# TS5USBC41.net
KiCad netlist of a schematic drawn in Altium Designer
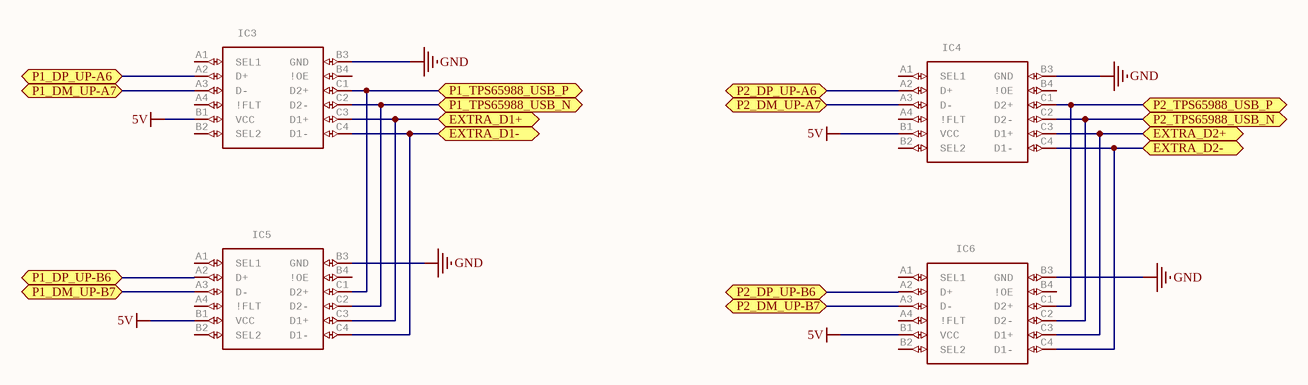
[diagram p0: TS5USBC41.SchDoc]

(export (version "E")
  (design (tool "Eeschema 10.0.6"))
  (components
    (comp (ref "IC3")
      (value "Dual 2:1 USB 2.0 Mux/DeMux or Single Ended Cross Switch With 20-V/24-V OVP   Source:  Datasheet")
      (footprint "BGA12C40P4X3_160X120X62")
      (fields
        (field (name "MANUFACTURER_PART_NUMBER") "TS5USBC410IYFFR")
        (field (name "MOUSER_PART_NUMBER") "595-TS5USBC410IYFFR")
      )
      (libsource (lib "TS5USBC410IYFFR.Library") (part "TS5USBC410IYFFR"))
    )
    (comp (ref "IC4")
      (value "Dual 2:1 USB 2.0 Mux/DeMux or Single Ended Cross Switch With 20-V/24-V OVP   Source:  Datasheet")
      (footprint "BGA12C40P4X3_160X120X62")
      (fields
        (field (name "MANUFACTURER_PART_NUMBER") "TS5USBC410IYFFR")
        (field (name "MOUSER_PART_NUMBER") "595-TS5USBC410IYFFR")
      )
      (libsource (lib "TS5USBC410IYFFR.Library") (part "TS5USBC410IYFFR"))
    )
    (comp (ref "IC5")
      (value "Dual 2:1 USB 2.0 Mux/DeMux or Single Ended Cross Switch With 20-V/24-V OVP   Source:  Datasheet")
      (footprint "BGA12C40P4X3_160X120X62")
      (fields
        (field (name "MANUFACTURER_PART_NUMBER") "TS5USBC410IYFFR")
        (field (name "MOUSER_PART_NUMBER") "595-TS5USBC410IYFFR")
      )
      (libsource (lib "TS5USBC410IYFFR.Library") (part "TS5USBC410IYFFR"))
    )
    (comp (ref "IC6")
      (value "Dual 2:1 USB 2.0 Mux/DeMux or Single Ended Cross Switch With 20-V/24-V OVP   Source:  Datasheet")
      (footprint "BGA12C40P4X3_160X120X62")
      (fields
        (field (name "MANUFACTURER_PART_NUMBER") "TS5USBC410IYFFR")
        (field (name "MOUSER_PART_NUMBER") "595-TS5USBC410IYFFR")
      )
      (libsource (lib "TS5USBC410IYFFR.Library") (part "TS5USBC410IYFFR"))
    )
  )
  (nets
    (net (code "1") (name "/EXTRA_D1+") (class "Default")
      (node (ref "IC3") (pin "C3") (pinfunction "D1+_C3") (pintype "bidirectional"))
      (node (ref "IC5") (pin "C3") (pinfunction "D1+_C3") (pintype "bidirectional"))
    )
    (net (code "2") (name "/EXTRA_D1-") (class "Default")
      (node (ref "IC3") (pin "C4") (pinfunction "D1-_C4") (pintype "bidirectional"))
      (node (ref "IC5") (pin "C4") (pinfunction "D1-_C4") (pintype "bidirectional"))
    )
    (net (code "3") (name "/EXTRA_D2+") (class "Default")
      (node (ref "IC4") (pin "C3") (pinfunction "D1+_C3") (pintype "bidirectional"))
      (node (ref "IC6") (pin "C3") (pinfunction "D1+_C3") (pintype "bidirectional"))
    )
    (net (code "4") (name "/EXTRA_D2-") (class "Default")
      (node (ref "IC4") (pin "C4") (pinfunction "D1-_C4") (pintype "bidirectional"))
      (node (ref "IC6") (pin "C4") (pinfunction "D1-_C4") (pintype "bidirectional"))
    )
    (net (code "5") (name "/P1_DM_UP-A7") (class "Default")
      (node (ref "IC3") (pin "A3") (pinfunction "D-_A3") (pintype "bidirectional"))
    )
    (net (code "6") (name "/P1_DM_UP-B7") (class "Default")
      (node (ref "IC5") (pin "A3") (pinfunction "D-_A3") (pintype "bidirectional"))
    )
    (net (code "7") (name "/P1_DP_UP-A6") (class "Default")
      (node (ref "IC3") (pin "A2") (pinfunction "D+_A2") (pintype "bidirectional"))
    )
    (net (code "8") (name "/P1_DP_UP-B6") (class "Default")
      (node (ref "IC5") (pin "A2") (pinfunction "D+_A2") (pintype "bidirectional"))
    )
    (net (code "9") (name "/P1_TPS65988_USB_N") (class "Default")
      (node (ref "IC3") (pin "C2") (pinfunction "D2-_C2") (pintype "bidirectional"))
      (node (ref "IC5") (pin "C2") (pinfunction "D2-_C2") (pintype "bidirectional"))
    )
    (net (code "10") (name "/P1_TPS65988_USB_P") (class "Default")
      (node (ref "IC3") (pin "C1") (pinfunction "D2+_C1") (pintype "bidirectional"))
      (node (ref "IC5") (pin "C1") (pinfunction "D2+_C1") (pintype "bidirectional"))
    )
    (net (code "11") (name "/P2_DM_UP-A7") (class "Default")
      (node (ref "IC4") (pin "A3") (pinfunction "D-_A3") (pintype "bidirectional"))
    )
    (net (code "12") (name "/P2_DM_UP-B7") (class "Default")
      (node (ref "IC6") (pin "A3") (pinfunction "D-_A3") (pintype "bidirectional"))
    )
    (net (code "13") (name "/P2_DP_UP-A6") (class "Default")
      (node (ref "IC4") (pin "A2") (pinfunction "D+_A2") (pintype "bidirectional"))
    )
    (net (code "14") (name "/P2_DP_UP-B6") (class "Default")
      (node (ref "IC6") (pin "A2") (pinfunction "D+_A2") (pintype "bidirectional"))
    )
    (net (code "15") (name "/P2_TPS65988_USB_N") (class "Default")
      (node (ref "IC4") (pin "C2") (pinfunction "D2-_C2") (pintype "bidirectional"))
      (node (ref "IC6") (pin "C2") (pinfunction "D2-_C2") (pintype "bidirectional"))
    )
    (net (code "16") (name "/P2_TPS65988_USB_P") (class "Default")
      (node (ref "IC4") (pin "C1") (pinfunction "D2+_C1") (pintype "bidirectional"))
      (node (ref "IC6") (pin "C1") (pinfunction "D2+_C1") (pintype "bidirectional"))
    )
    (net (code "17") (name "5V") (class "Default")
      (node (ref "IC3") (pin "B1") (pinfunction "VCC_B1") (pintype "bidirectional"))
      (node (ref "IC4") (pin "B1") (pinfunction "VCC_B1") (pintype "bidirectional"))
      (node (ref "IC5") (pin "B1") (pinfunction "VCC_B1") (pintype "bidirectional"))
      (node (ref "IC6") (pin "B1") (pinfunction "VCC_B1") (pintype "bidirectional"))
    )
    (net (code "18") (name "GND") (class "Default")
      (node (ref "IC3") (pin "B3") (pinfunction "GND_B3") (pintype "bidirectional"))
      (node (ref "IC4") (pin "B3") (pinfunction "GND_B3") (pintype "bidirectional"))
      (node (ref "IC5") (pin "B3") (pinfunction "GND_B3") (pintype "bidirectional"))
      (node (ref "IC6") (pin "B3") (pinfunction "GND_B3") (pintype "bidirectional"))
    )
    (net (code "19") (name "unconnected-(IC3-!FLT-PadA4)") (class "Default")
      (node (ref "IC3") (pin "A4") (pinfunction "!FLT_A4") (pintype "bidirectional"))
    )
    (net (code "20") (name "unconnected-(IC3-!OE-PadB4)") (class "Default")
      (node (ref "IC3") (pin "B4") (pinfunction "!OE_B4") (pintype "bidirectional"))
    )
    (net (code "21") (name "unconnected-(IC3-SEL1-PadA1)") (class "Default")
      (node (ref "IC3") (pin "A1") (pinfunction "SEL1_A1") (pintype "bidirectional"))
    )
    (net (code "22") (name "unconnected-(IC3-SEL2-PadB2)") (class "Default")
      (node (ref "IC3") (pin "B2") (pinfunction "SEL2_B2") (pintype "bidirectional"))
    )
    (net (code "23") (name "unconnected-(IC4-!FLT-PadA4)") (class "Default")
      (node (ref "IC4") (pin "A4") (pinfunction "!FLT_A4") (pintype "bidirectional"))
    )
    (net (code "24") (name "unconnected-(IC4-!OE-PadB4)") (class "Default")
      (node (ref "IC4") (pin "B4") (pinfunction "!OE_B4") (pintype "bidirectional"))
    )
    (net (code "25") (name "unconnected-(IC4-SEL1-PadA1)") (class "Default")
      (node (ref "IC4") (pin "A1") (pinfunction "SEL1_A1") (pintype "bidirectional"))
    )
    (net (code "26") (name "unconnected-(IC4-SEL2-PadB2)") (class "Default")
      (node (ref "IC4") (pin "B2") (pinfunction "SEL2_B2") (pintype "bidirectional"))
    )
    (net (code "27") (name "unconnected-(IC5-!FLT-PadA4)") (class "Default")
      (node (ref "IC5") (pin "A4") (pinfunction "!FLT_A4") (pintype "bidirectional"))
    )
    (net (code "28") (name "unconnected-(IC5-!OE-PadB4)") (class "Default")
      (node (ref "IC5") (pin "B4") (pinfunction "!OE_B4") (pintype "bidirectional"))
    )
    (net (code "29") (name "unconnected-(IC5-SEL1-PadA1)") (class "Default")
      (node (ref "IC5") (pin "A1") (pinfunction "SEL1_A1") (pintype "bidirectional"))
    )
    (net (code "30") (name "unconnected-(IC5-SEL2-PadB2)") (class "Default")
      (node (ref "IC5") (pin "B2") (pinfunction "SEL2_B2") (pintype "bidirectional"))
    )
    (net (code "31") (name "unconnected-(IC6-!FLT-PadA4)") (class "Default")
      (node (ref "IC6") (pin "A4") (pinfunction "!FLT_A4") (pintype "bidirectional"))
    )
    (net (code "32") (name "unconnected-(IC6-!OE-PadB4)") (class "Default")
      (node (ref "IC6") (pin "B4") (pinfunction "!OE_B4") (pintype "bidirectional"))
    )
    (net (code "33") (name "unconnected-(IC6-SEL1-PadA1)") (class "Default")
      (node (ref "IC6") (pin "A1") (pinfunction "SEL1_A1") (pintype "bidirectional"))
    )
    (net (code "34") (name "unconnected-(IC6-SEL2-PadB2)") (class "Default")
      (node (ref "IC6") (pin "B2") (pinfunction "SEL2_B2") (pintype "bidirectional"))
    )
  )
)
